# MiMo-Light-V2_0.net
KiCad netlist of a schematic drawn in EAGLE
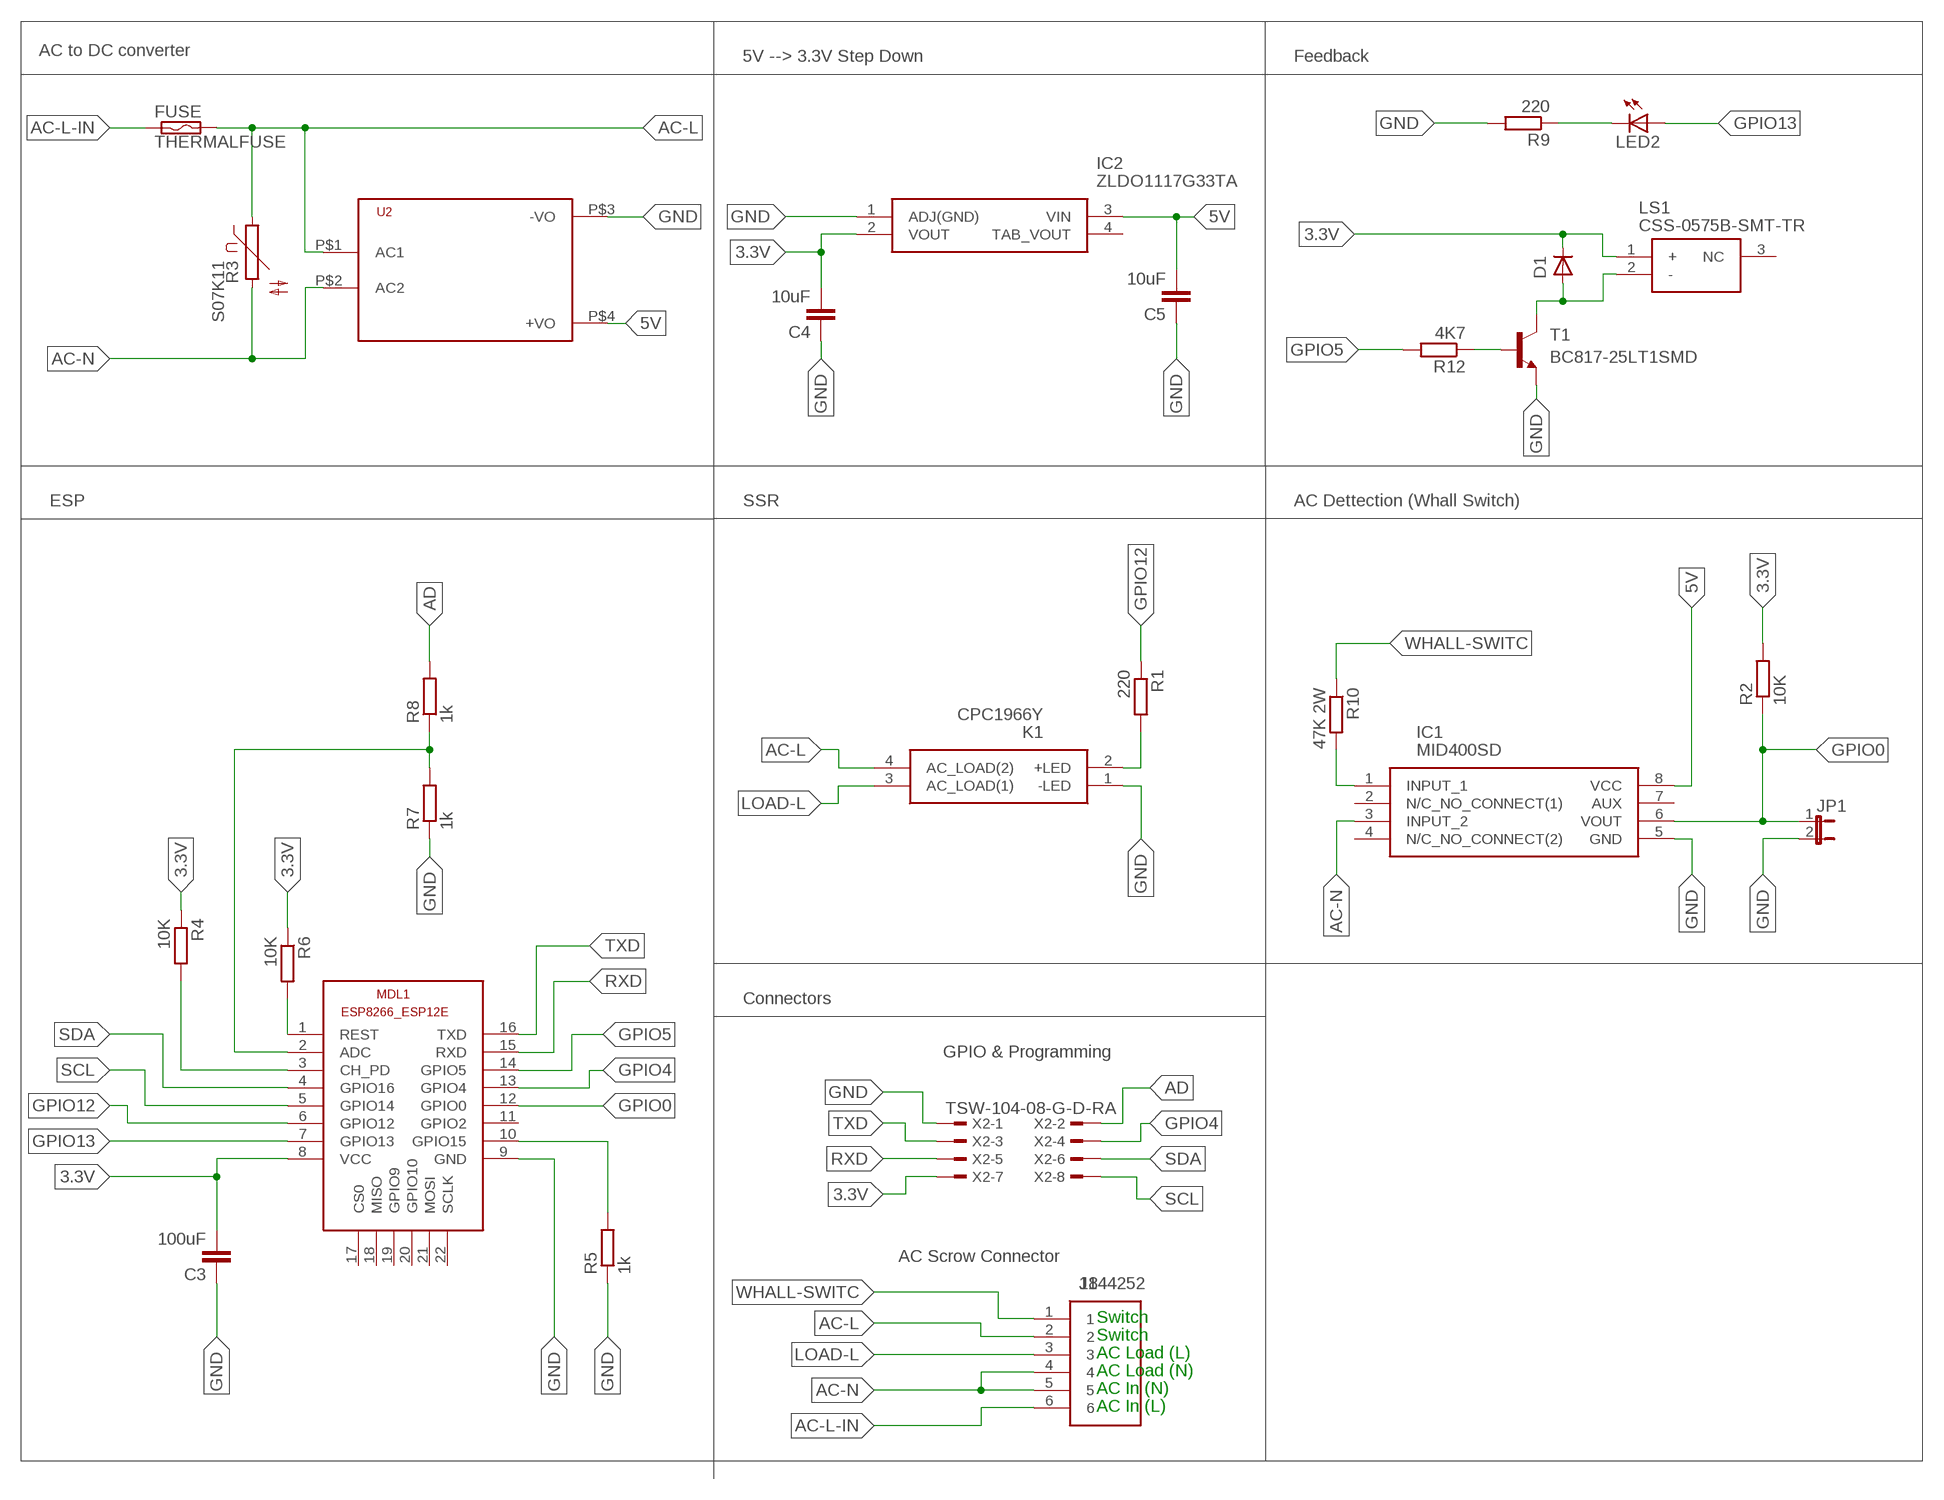
[diagram p0: schematic, sheet 1]

(export (version "E")
  (design (tool "Eeschema 10.0.6"))
  (components
    (comp (ref "C3")
      (value "100uF")
      (footprint "eagle-import:1210")
      (libsource (lib "eagle-import") (part "CAP1210"))
    )
    (comp (ref "C4")
      (value "10uF")
      (footprint "eagle-import:1206")
      (libsource (lib "eagle-import") (part "CAP1206"))
    )
    (comp (ref "C5")
      (value "10uF")
      (footprint "eagle-import:1206")
      (libsource (lib "eagle-import") (part "CAP1206"))
    )
    (comp (ref "D1")
      (value "DIODE-MINIMELF")
      (footprint "eagle-import:MINIMELF")
      (libsource (lib "eagle-import") (part "DIODE-MINIMELF"))
    )
    (comp (ref "FUSE")
      (value "THERMALFUSE")
      (footprint "eagle-import:TE5")
      (libsource (lib "eagle-import") (part "THERMALFUSE12MM"))
    )
    (comp (ref "IC1")
      (value "MID400SD")
      (footprint "eagle-import:SOP254P1030X508-8N")
      (fields (field (name "RS_PART_NUMBER") "8064169P"))
      (libsource (lib "eagle-import") (part "MID400SD"))
    )
    (comp (ref "IC2")
      (value "ZLDO1117G33TA")
      (footprint "eagle-import:SOT230P700X180-4N")
      (fields (field (name "RS_PART_NUMBER") "7515183P"))
      (libsource (lib "eagle-import") (part "ZLDO1117G33TA"))
    )
    (comp (ref "J1")
      (value "1844252")
      (footprint "eagle-import:SHDR6W100P0X350_1X6_2240X920X7")
      (fields (field (name "RS_PART_NUMBER") "8042257"))
      (libsource (lib "eagle-import") (part "1844252"))
    )
    (comp (ref "JP1")
      (value "JP1E")
      (footprint "eagle-import:JP1")
      (libsource (lib "eagle-import") (part "JP1E"))
    )
    (comp (ref "K1")
      (value "CPC1966Y")
      (footprint "eagle-import:CPC1966Y")
      (fields (field (name "RS_PART_NUMBER") "9061091"))
      (libsource (lib "eagle-import") (part "CPC1966Y"))
    )
    (comp (ref "LED2")
      (value "LEDCHIPLED_1206")
      (footprint "eagle-import:CHIPLED_1206")
      (libsource (lib "eagle-import") (part "LEDCHIPLED_1206"))
    )
    (comp (ref "LS1")
      (value "CSS-0575B-SMT-TR")
      (footprint "eagle-import:CSS-0575B-SMT-TR")
      (libsource (lib "eagle-import") (part "CSS-0575B-SMT-TR"))
    )
    (comp (ref "MDL1")
      (value "ESP8266-12EESP8266-ESP12E")
      (footprint "eagle-import:ESP8266-ESP12E")
      (libsource (lib "eagle-import") (part "ESP8266-12EESP8266-ESP12E"))
    )
    (comp (ref "R1")
      (value "220")
      (footprint "eagle-import:R1206")
      (libsource (lib "eagle-import") (part "RR1206"))
    )
    (comp (ref "R2")
      (value "10K")
      (footprint "eagle-import:R1206")
      (libsource (lib "eagle-import") (part "RR1206"))
    )
    (comp (ref "R3")
      (value "S07K11")
      (footprint "eagle-import:S07K11")
      (libsource (lib "eagle-import") (part "S07K11"))
    )
    (comp (ref "R4")
      (value "10K")
      (footprint "eagle-import:R1206")
      (libsource (lib "eagle-import") (part "RR1206"))
    )
    (comp (ref "R5")
      (value "1k")
      (footprint "eagle-import:R1206")
      (libsource (lib "eagle-import") (part "RR1206"))
    )
    (comp (ref "R6")
      (value "10K")
      (footprint "eagle-import:R1206")
      (libsource (lib "eagle-import") (part "RR1206"))
    )
    (comp (ref "R7")
      (value "1k")
      (footprint "eagle-import:R1206")
      (libsource (lib "eagle-import") (part "RR1206"))
    )
    (comp (ref "R8")
      (value "1k")
      (footprint "eagle-import:R1206")
      (libsource (lib "eagle-import") (part "RR1206"))
    )
    (comp (ref "R9")
      (value "220")
      (footprint "eagle-import:R1206")
      (libsource (lib "eagle-import") (part "RR1206"))
    )
    (comp (ref "R10")
      (value "47K 2W")
      (footprint "eagle-import:R2512")
      (libsource (lib "eagle-import") (part "RR2512"))
    )
    (comp (ref "R12")
      (value "4K7")
      (footprint "eagle-import:R1206")
      (libsource (lib "eagle-import") (part "RR1206"))
    )
    (comp (ref "T1")
      (value "BC817-25LT1SMD")
      (footprint "eagle-import:SOT23-BEC")
      (libsource (lib "eagle-import") (part "BC817SMD-25LT1"))
    )
    (comp (ref "U2")
      (value "HLK-PM013W")
      (footprint "eagle-import:HLK-PM01")
      (libsource (lib "eagle-import") (part "HLK-PM013W"))
    )
    (comp (ref "X2")
      (value "TSW-104-08-G-D-RA")
      (footprint "eagle-import:TSW-104-08-G-D-RA")
      (fields (field (name "MF") "Samtec Inc."))
      (libsource (lib "eagle-import") (part "TSW-104--G-D-RA08"))
    )
  )
  (nets
    (net (code "1") (name "3.3V") (class "Default")
      (node (ref "C3") (pin "2") (pinfunction "2_2") (pintype "passive"))
      (node (ref "C4") (pin "2") (pinfunction "2_2") (pintype "passive"))
      (node (ref "D1") (pin "C") (pinfunction "C_C") (pintype "passive"))
      (node (ref "IC2") (pin "2") (pinfunction "VOUT_2") (pintype "output"))
      (node (ref "LS1") (pin "1") (pinfunction "+_1") (pintype "input"))
      (node (ref "MDL1") (pin "8") (pinfunction "VCC_8") (pintype "bidirectional"))
      (node (ref "R2") (pin "2") (pinfunction "2_2") (pintype "passive"))
      (node (ref "R4") (pin "1") (pinfunction "1_1") (pintype "passive"))
      (node (ref "R6") (pin "1") (pinfunction "1_1") (pintype "passive"))
      (node (ref "X2") (pin "7") (pinfunction "1_7") (pintype "passive"))
    )
    (net (code "2") (name "5V") (class "Default")
      (node (ref "C5") (pin "2") (pinfunction "2_2") (pintype "passive"))
      (node (ref "IC1") (pin "8") (pinfunction "VCC_8") (pintype "input"))
      (node (ref "IC2") (pin "3") (pinfunction "VIN_3") (pintype "input"))
      (node (ref "U2") (pin "P$4") (pinfunction "+VO_P$4") (pintype "bidirectional"))
    )
    (net (code "3") (name "AC-L") (class "Default")
      (node (ref "FUSE") (pin "2") (pinfunction "2_2") (pintype "passive"))
      (node (ref "J1") (pin "2") (pinfunction "2_2") (pintype "bidirectional"))
      (node (ref "K1") (pin "4") (pinfunction "AC_LOAD(2)_4") (pintype "bidirectional"))
      (node (ref "R3") (pin "1") (pinfunction "1_1") (pintype "passive"))
      (node (ref "U2") (pin "P$1") (pinfunction "AC1_P$1") (pintype "bidirectional"))
    )
    (net (code "4") (name "AC-L-IN") (class "Default")
      (node (ref "FUSE") (pin "1") (pinfunction "1_1") (pintype "passive"))
      (node (ref "J1") (pin "6") (pinfunction "6_6") (pintype "bidirectional"))
    )
    (net (code "5") (name "AC-N") (class "Default")
      (node (ref "IC1") (pin "3") (pinfunction "INPUT_2_3") (pintype "input"))
      (node (ref "J1") (pin "4") (pinfunction "4_4") (pintype "bidirectional"))
      (node (ref "J1") (pin "5") (pinfunction "5_5") (pintype "bidirectional"))
      (node (ref "R3") (pin "2") (pinfunction "2_2") (pintype "passive"))
      (node (ref "U2") (pin "P$2") (pinfunction "AC2_P$2") (pintype "bidirectional"))
    )
    (net (code "6") (name "AD") (class "Default")
      (node (ref "R8") (pin "2") (pinfunction "2_2") (pintype "passive"))
      (node (ref "X2") (pin "2") (pinfunction "1_2") (pintype "passive"))
    )
    (net (code "7") (name "GND") (class "Default")
      (node (ref "C3") (pin "1") (pinfunction "1_1") (pintype "passive"))
      (node (ref "C4") (pin "1") (pinfunction "1_1") (pintype "passive"))
      (node (ref "C5") (pin "1") (pinfunction "1_1") (pintype "passive"))
      (node (ref "IC1") (pin "5") (pinfunction "GND_5") (pintype "input"))
      (node (ref "IC2") (pin "1") (pinfunction "ADJ(GND)_1") (pintype "power_in"))
      (node (ref "JP1") (pin "2") (pinfunction "2_2") (pintype "passive"))
      (node (ref "K1") (pin "1") (pinfunction "-LED_1") (pintype "bidirectional"))
      (node (ref "MDL1") (pin "9") (pinfunction "GND_9") (pintype "bidirectional"))
      (node (ref "R5") (pin "1") (pinfunction "1_1") (pintype "passive"))
      (node (ref "R7") (pin "1") (pinfunction "1_1") (pintype "passive"))
      (node (ref "R9") (pin "2") (pinfunction "2_2") (pintype "passive"))
      (node (ref "T1") (pin "E") (pinfunction "E_E") (pintype "passive"))
      (node (ref "U2") (pin "P$3") (pinfunction "-VO_P$3") (pintype "bidirectional"))
      (node (ref "X2") (pin "1") (pinfunction "1_1") (pintype "passive"))
    )
    (net (code "8") (name "GPIO0") (class "Default")
      (node (ref "IC1") (pin "6") (pinfunction "VOUT_6") (pintype "input"))
      (node (ref "JP1") (pin "1") (pinfunction "1_1") (pintype "passive"))
      (node (ref "MDL1") (pin "12") (pinfunction "GPIO0_12") (pintype "bidirectional"))
      (node (ref "R2") (pin "1") (pinfunction "1_1") (pintype "passive"))
    )
    (net (code "9") (name "GPIO4") (class "Default")
      (node (ref "MDL1") (pin "13") (pinfunction "GPIO4_13") (pintype "bidirectional"))
      (node (ref "X2") (pin "4") (pinfunction "1_4") (pintype "passive"))
    )
    (net (code "10") (name "GPIO5") (class "Default")
      (node (ref "MDL1") (pin "14") (pinfunction "GPIO5_14") (pintype "bidirectional"))
      (node (ref "R12") (pin "2") (pinfunction "2_2") (pintype "passive"))
    )
    (net (code "11") (name "GPIO12") (class "Default")
      (node (ref "MDL1") (pin "6") (pinfunction "GPIO12_6") (pintype "bidirectional"))
      (node (ref "R1") (pin "1") (pinfunction "1_1") (pintype "passive"))
    )
    (net (code "12") (name "GPIO13") (class "Default")
      (node (ref "LED2") (pin "A") (pinfunction "A_A") (pintype "passive"))
      (node (ref "MDL1") (pin "7") (pinfunction "GPIO13_7") (pintype "bidirectional"))
    )
    (net (code "13") (name "LOAD-L") (class "Default")
      (node (ref "J1") (pin "3") (pinfunction "3_3") (pintype "bidirectional"))
      (node (ref "K1") (pin "3") (pinfunction "AC_LOAD(1)_3") (pintype "bidirectional"))
    )
    (net (code "14") (name "Net-(IC1-INPUT_1)") (class "Default")
      (node (ref "IC1") (pin "1") (pinfunction "INPUT_1_1") (pintype "input"))
      (node (ref "R10") (pin "2") (pinfunction "2_2") (pintype "passive"))
    )
    (net (code "15") (name "Net-(K1-+LED)") (class "Default")
      (node (ref "K1") (pin "2") (pinfunction "+LED_2") (pintype "bidirectional"))
      (node (ref "R1") (pin "2") (pinfunction "2_2") (pintype "passive"))
    )
    (net (code "16") (name "Net-(LED2-PadC)") (class "Default")
      (node (ref "LED2") (pin "C") (pinfunction "C_C") (pintype "passive"))
      (node (ref "R9") (pin "1") (pinfunction "1_1") (pintype "passive"))
    )
    (net (code "17") (name "Net-(LS1--)") (class "Default")
      (node (ref "D1") (pin "A") (pinfunction "A_A") (pintype "passive"))
      (node (ref "LS1") (pin "2") (pinfunction "-_2") (pintype "input"))
      (node (ref "T1") (pin "C") (pinfunction "C_C") (pintype "passive"))
    )
    (net (code "18") (name "Net-(MDL1-ADC)") (class "Default")
      (node (ref "MDL1") (pin "2") (pinfunction "ADC_2") (pintype "bidirectional"))
      (node (ref "R7") (pin "2") (pinfunction "2_2") (pintype "passive"))
      (node (ref "R8") (pin "1") (pinfunction "1_1") (pintype "passive"))
    )
    (net (code "19") (name "Net-(MDL1-CH_PD)") (class "Default")
      (node (ref "MDL1") (pin "3") (pinfunction "CH_PD_3") (pintype "bidirectional"))
      (node (ref "R4") (pin "2") (pinfunction "2_2") (pintype "passive"))
    )
    (net (code "20") (name "Net-(MDL1-GPIO15)") (class "Default")
      (node (ref "MDL1") (pin "10") (pinfunction "GPIO15_10") (pintype "bidirectional"))
      (node (ref "R5") (pin "2") (pinfunction "2_2") (pintype "passive"))
    )
    (net (code "21") (name "Net-(MDL1-REST)") (class "Default")
      (node (ref "MDL1") (pin "1") (pinfunction "REST_1") (pintype "bidirectional"))
      (node (ref "R6") (pin "2") (pinfunction "2_2") (pintype "passive"))
    )
    (net (code "22") (name "Net-(R12-Pad1)") (class "Default")
      (node (ref "R12") (pin "1") (pinfunction "1_1") (pintype "passive"))
      (node (ref "T1") (pin "B") (pinfunction "B_B") (pintype "passive"))
    )
    (net (code "23") (name "RXD") (class "Default")
      (node (ref "MDL1") (pin "15") (pinfunction "RXD_15") (pintype "bidirectional"))
      (node (ref "X2") (pin "5") (pinfunction "1_5") (pintype "passive"))
    )
    (net (code "24") (name "SCL") (class "Default")
      (node (ref "MDL1") (pin "5") (pinfunction "GPIO14_5") (pintype "bidirectional"))
      (node (ref "X2") (pin "8") (pinfunction "1_8") (pintype "passive"))
    )
    (net (code "25") (name "SDA") (class "Default")
      (node (ref "MDL1") (pin "4") (pinfunction "GPIO16_4") (pintype "bidirectional"))
      (node (ref "X2") (pin "6") (pinfunction "1_6") (pintype "passive"))
    )
    (net (code "26") (name "TXD") (class "Default")
      (node (ref "MDL1") (pin "16") (pinfunction "TXD_16") (pintype "bidirectional"))
      (node (ref "X2") (pin "3") (pinfunction "1_3") (pintype "passive"))
    )
    (net (code "27") (name "WHALL-SWITC") (class "Default")
      (node (ref "J1") (pin "1") (pinfunction "1_1") (pintype "bidirectional"))
      (node (ref "R10") (pin "1") (pinfunction "1_1") (pintype "passive"))
    )
    (net (code "28") (name "unconnected-(IC1-AUX-Pad7)") (class "Default")
      (node (ref "IC1") (pin "7") (pinfunction "AUX_7") (pintype "input"))
    )
    (net (code "29") (name "unconnected-(IC1-N{slash}C_NO_CONNECT(1)-Pad2)") (class "Default")
      (node (ref "IC1") (pin "2") (pinfunction "N/C_NO_CONNECT(1)_2") (pintype "input"))
    )
    (net (code "30") (name "unconnected-(IC1-N{slash}C_NO_CONNECT(2)-Pad4)") (class "Default")
      (node (ref "IC1") (pin "4") (pinfunction "N/C_NO_CONNECT(2)_4") (pintype "input"))
    )
    (net (code "31") (name "unconnected-(IC2-TAB_VOUT-Pad4)") (class "Default")
      (node (ref "IC2") (pin "4") (pinfunction "TAB_VOUT_4") (pintype "output"))
    )
    (net (code "32") (name "unconnected-(LS1-NC-Pad3)") (class "Default")
      (node (ref "LS1") (pin "3") (pinfunction "NC_3") (pintype "input"))
    )
    (net (code "33") (name "unconnected-(MDL1-CS0-Pad17)") (class "Default")
      (node (ref "MDL1") (pin "17") (pinfunction "CS0_17") (pintype "bidirectional"))
    )
    (net (code "34") (name "unconnected-(MDL1-GPIO2-Pad11)") (class "Default")
      (node (ref "MDL1") (pin "11") (pinfunction "GPIO2_11") (pintype "bidirectional"))
    )
    (net (code "35") (name "unconnected-(MDL1-GPIO9-Pad19)") (class "Default")
      (node (ref "MDL1") (pin "19") (pinfunction "GPIO9_19") (pintype "bidirectional"))
    )
    (net (code "36") (name "unconnected-(MDL1-GPIO10-Pad20)") (class "Default")
      (node (ref "MDL1") (pin "20") (pinfunction "GPIO10_20") (pintype "bidirectional"))
    )
    (net (code "37") (name "unconnected-(MDL1-MISO-Pad18)") (class "Default")
      (node (ref "MDL1") (pin "18") (pinfunction "MISO_18") (pintype "bidirectional"))
    )
    (net (code "38") (name "unconnected-(MDL1-MOSI-Pad21)") (class "Default")
      (node (ref "MDL1") (pin "21") (pinfunction "MOSI_21") (pintype "bidirectional"))
    )
    (net (code "39") (name "unconnected-(MDL1-SCLK-Pad22)") (class "Default")
      (node (ref "MDL1") (pin "22") (pinfunction "SCLK_22") (pintype "bidirectional"))
    )
  )
)
